# ArbPwrBoost_P7.net
KiCad netlist of a schematic drawn in Altium Designer
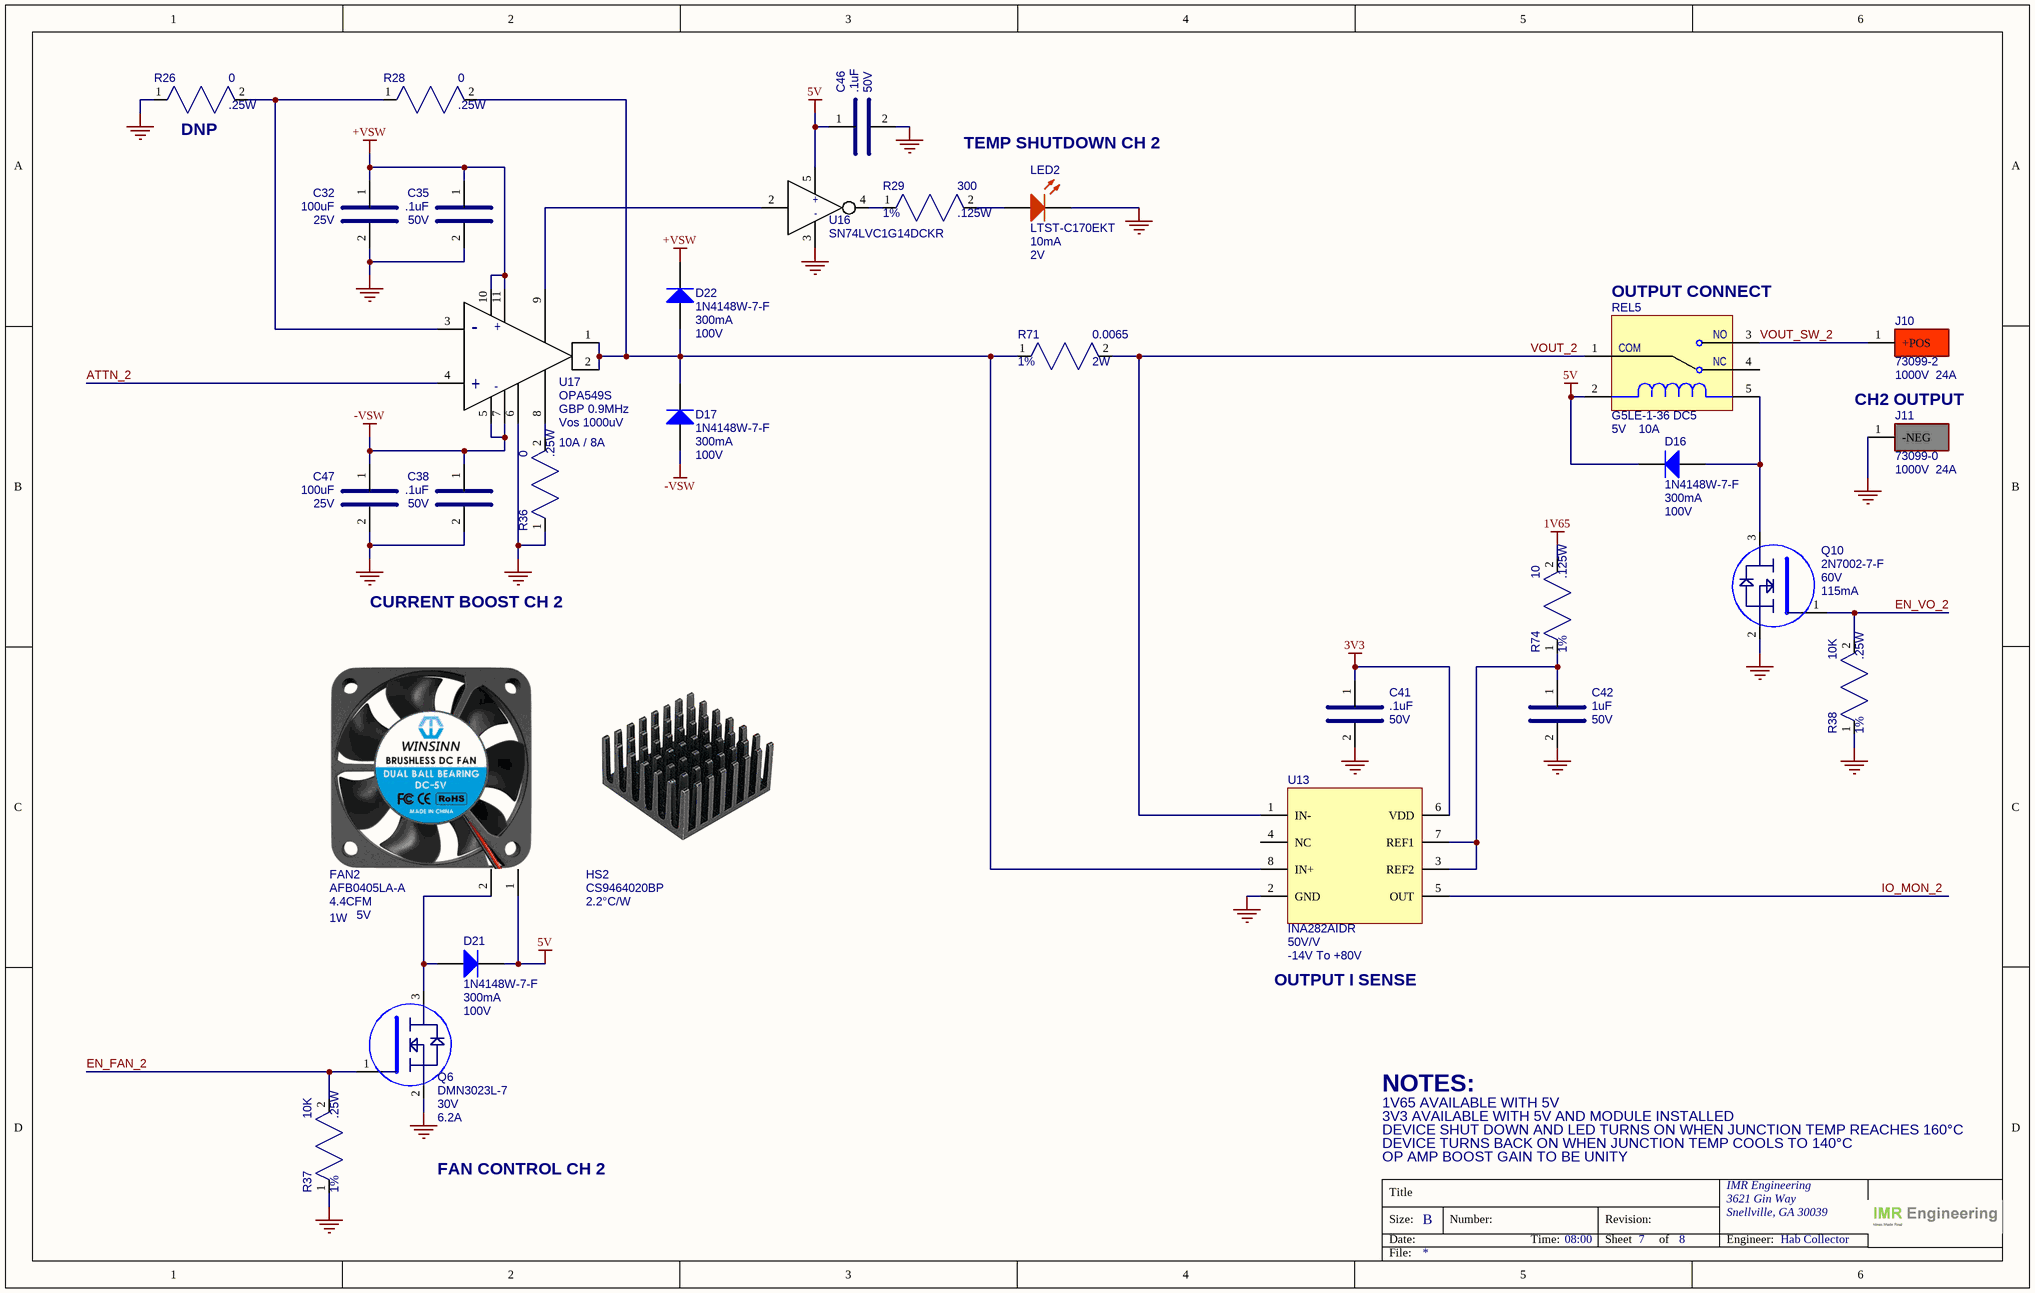
[diagram p0: ArbPwrBoost_P7.SchDoc]

(export (version "E")
  (design (tool "Eeschema 10.0.6"))
  (components
    (comp (ref "C32")
      (value "100uF")
      (footprint "CAPC6153X670N")
      (description "CAP CER 100UF 25V X7S SMD")
      (fields
        (field (name "MFG") "Murata Electronics")
        (field (name "VOLTAGE") "25V")
        (field (name "Comment") "KCM55WC71E107MH13L")
      )
      (libsource (lib "IMR_LIB_SCH_R2") (part "CAP_SMD_100UF_25V_SMD"))
    )
    (comp (ref "C35")
      (value ".1uF")
      (footprint "CAP_0805")
      (description "CAP CER 0.1UF 50V X7R 0805")
      (fields
        (field (name "MFG") "KYOCERA AVX")
        (field (name "VOLTAGE") "50V")
        (field (name "Comment") "KGM21NR71H104KT")
      )
      (libsource (lib "IMR_LIB_SCH_R2") (part "CAP_SMD_0.1UF_50V_0805"))
    )
    (comp (ref "C38")
      (value ".1uF")
      (footprint "CAP_0805")
      (description "CAP CER 0.1UF 50V X7R 0805")
      (fields
        (field (name "MFG") "KYOCERA AVX")
        (field (name "VOLTAGE") "50V")
        (field (name "Comment") "KGM21NR71H104KT")
      )
      (libsource (lib "IMR_LIB_SCH_R2") (part "CAP_SMD_0.1UF_50V_0805"))
    )
    (comp (ref "C41")
      (value ".1uF")
      (footprint "CAP_0805")
      (description "CAP CER 0.1UF 50V X7R 0805")
      (fields
        (field (name "MFG") "KYOCERA AVX")
        (field (name "VOLTAGE") "50V")
        (field (name "Comment") "KGM21NR71H104KT")
      )
      (libsource (lib "IMR_LIB_SCH_R2") (part "CAP_SMD_0.1UF_50V_0805"))
    )
    (comp (ref "C42")
      (value "1uF")
      (footprint "CAP_0805")
      (description "CAP CER 1UF 50V X7R 0805")
      (fields
        (field (name "MFG") "KYOCERA AVX")
        (field (name "VOLTAGE") "50V")
        (field (name "Comment") "08055C105K4T2A")
      )
      (libsource (lib "IMR_LIB_SCH_R2") (part "CAP_SMD_1UF_50V_0805"))
    )
    (comp (ref "C46")
      (value ".1uF")
      (footprint "CAP_0805")
      (description "CAP CER 0.1UF 50V X7R 0805")
      (fields
        (field (name "MFG") "KYOCERA AVX")
        (field (name "VOLTAGE") "50V")
        (field (name "Comment") "KGM21NR71H104KT")
      )
      (libsource (lib "IMR_LIB_SCH_R2") (part "CAP_SMD_0.1UF_50V_0805"))
    )
    (comp (ref "C47")
      (value "100uF")
      (footprint "CAPC6153X670N")
      (description "CAP CER 100UF 25V X7S SMD")
      (fields
        (field (name "MFG") "Murata Electronics")
        (field (name "VOLTAGE") "25V")
        (field (name "Comment") "KCM55WC71E107MH13L")
      )
      (libsource (lib "IMR_LIB_SCH_R2") (part "CAP_SMD_100UF_25V_SMD"))
    )
    (comp (ref "D16")
      (value "100V")
      (footprint "SOD123")
      (description "RELAY REED SPDT 250MA 5V")
      (fields
        (field (name "MFG") "Diodes Inc")
        (field (name "MFG_PN") "1N4148W-7-F")
        (field (name "CURRENT") "300mA")
        (field (name "Comment") "1N4148W-7-F")
      )
      (libsource (lib "IMR_LIB_SCH_R2") (part "DIODE_1N4148W-7-F"))
    )
    (comp (ref "D17")
      (value "100V")
      (footprint "SOD123")
      (description "RELAY REED SPDT 250MA 5V")
      (fields
        (field (name "MFG") "Diodes Inc")
        (field (name "MFG_PN") "1N4148W-7-F")
        (field (name "CURRENT") "300mA")
        (field (name "Comment") "1N4148W-7-F")
      )
      (libsource (lib "IMR_LIB_SCH_R2") (part "DIODE_1N4148W-7-F"))
    )
    (comp (ref "D21")
      (value "100V")
      (footprint "SOD123")
      (description "RELAY REED SPDT 250MA 5V")
      (fields
        (field (name "MFG") "Diodes Inc")
        (field (name "MFG_PN") "1N4148W-7-F")
        (field (name "CURRENT") "300mA")
        (field (name "Comment") "1N4148W-7-F")
      )
      (libsource (lib "IMR_LIB_SCH_R2") (part "DIODE_1N4148W-7-F"))
    )
    (comp (ref "D22")
      (value "100V")
      (footprint "SOD123")
      (description "RELAY REED SPDT 250MA 5V")
      (fields
        (field (name "MFG") "Diodes Inc")
        (field (name "MFG_PN") "1N4148W-7-F")
        (field (name "CURRENT") "300mA")
        (field (name "Comment") "1N4148W-7-F")
      )
      (libsource (lib "IMR_LIB_SCH_R2") (part "DIODE_1N4148W-7-F"))
    )
    (comp (ref "FAN2")
      (value "AFB0405LA-A")
      (footprint "FAN_AFB0405LA-A")
      (description "FAN AXIAL 40X10MM BALL 5VDC WIRE")
      (fields
        (field (name "MFG") "Delta Electronicis")
        (field (name "MFG_PN") "AFB0405LA-A")
        (field (name "AIR FLOW") "4.4CFM")
        (field (name "VOLTAGE") "5V")
        (field (name "POWER") "1W")
      )
      (libsource (lib "IMR_LIB_SCH_R2") (part "FAN_AFB0405LA-A"))
    )
    (comp (ref "HS2")
      (value "CS9464020BP")
      (footprint "HEATSINK_CS9464020BP")
      (description "Heat Sink Aluminum Top Mount")
      (fields
        (field (name "MFG") "Cooling Source")
        (field (name "MFG_PN") "CS9464020BP")
        (field (name "THERMAL RESISTANCE") "2.2°C/W")
      )
      (libsource (lib "IMR_LIB_SCH_R2") (part "HEATSINK_CS9464020BP"))
    )
    (comp (ref "J10")
      (value "1000V")
      (footprint "Pomona_73099-2")
      (description "CONN 4mm Banana Socket Right Angle PCB RED")
      (fields
        (field (name "MFG") "Pomona")
        (field (name "MFG_PN") "73099-2")
        (field (name "CURRENT") "24A")
        (field (name "Comment") "73099-2")
      )
      (libsource (lib "IMR_LIB_SCH_R2") (part "CONN_PANOMA_73099-2"))
    )
    (comp (ref "J11")
      (value "1000V")
      (footprint "Pomona_73099-0")
      (description "CONN 4mm Banana Socket Right Angle PCB BLK")
      (fields
        (field (name "MFG") "Pomona")
        (field (name "MFG_PN") "73099-0")
        (field (name "CURRENT") "24A")
        (field (name "Comment") "73099-0")
      )
      (libsource (lib "IMR_LIB_SCH_R2") (part "CONN_PANOMA_73099-0"))
    )
    (comp (ref "LED2")
      (value "2V")
      (footprint "LED_0805")
      (description "LED RED CLEAR SMD")
      (fields
        (field (name "MFG") "Diodes Inc")
        (field (name "MFG_PN") "LTST-C170EKT")
        (field (name "CURRENT") "10mA")
        (field (name "Comment") "LTST-C170EKT")
      )
      (libsource (lib "IMR_LIB_SCH_R2") (part "LED_RED_LTST-C170EKT"))
    )
    (comp (ref "Q6")
      (value "30V")
      (footprint "SOT-23")
      (description "MOSFET N-CH 30V 6.2A SOT23-3")
      (fields
        (field (name "MFG") "Diodes Inc")
        (field (name "MFG_PN") "DMN3023L-7")
        (field (name "CURRENT") "6.2A")
        (field (name "Comment") "DMN3023L-7")
      )
      (libsource (lib "IMR_LIB_SCH_R2") (part "MOSFET_NCH_DMN3023L-7"))
    )
    (comp (ref "Q10")
      (value "60V")
      (footprint "SOT-23")
      (description "MOSFET N-CH 60V 115MA SOT23-3")
      (fields
        (field (name "MFG") "Diodes Inc")
        (field (name "MFG_PN") "2N7002-7-F")
        (field (name "CURRENT") "115mA")
        (field (name "Comment") "2N7002-7-F")
      )
      (libsource (lib "IMR_LIB_SCH_R2") (part "MOSFET_NCH_2N7002-7-F"))
    )
    (comp (ref "R26")
      (value "0")
      (footprint "RES_0805")
      (description "RES SMD 0 OHM 1% 1/8W 0805")
      (fields (field (name "MFG") "Yageo") (field (name "TOLERANCE") "1%") (field (name "POWER") ".25W"))
      (libsource (lib "IMR_LIB_SCH_R2") (part "RES_SMD_0_0805_1/8W_1%"))
    )
    (comp (ref "R28")
      (value "0")
      (footprint "RES_0805")
      (description "RES SMD 0 OHM 1% 1/8W 0805")
      (fields (field (name "MFG") "Yageo") (field (name "TOLERANCE") "1%") (field (name "POWER") ".25W"))
      (libsource (lib "IMR_LIB_SCH_R2") (part "RES_SMD_0_0805_1/8W_1%"))
    )
    (comp (ref "R29")
      (value "300")
      (footprint "RES_0805")
      (description "RES SMD 300 OHM 1% 1/8W 0805")
      (fields
        (field (name "MFG") "Yageo")
        (field (name "POWER") ".125W")
        (field (name "TOLERANCE") "1%")
        (field (name "Comment") "RC0805FR-07300RL")
      )
      (libsource (lib "IMR_LIB_SCH_R2") (part "RES_SMD_300_0805_1/8W_1%"))
    )
    (comp (ref "R36")
      (value "0")
      (footprint "RES_0805")
      (description "RES SMD 0 OHM 1% 1/8W 0805")
      (fields (field (name "MFG") "Yageo") (field (name "TOLERANCE") "1%") (field (name "POWER") ".25W"))
      (libsource (lib "IMR_LIB_SCH_R2") (part "RES_SMD_0_0805_1/8W_1%"))
    )
    (comp (ref "R37")
      (value "10K")
      (footprint "RES_0805")
      (description "RES SMD 10K OHM 1% 1/4W 0805")
      (fields
        (field (name "MFG") "Yageo")
        (field (name "POWER") ".25W")
        (field (name "TOLERANCE") "1%")
        (field (name "Comment") "RC0805FR-7W10KL")
      )
      (libsource (lib "IMR_LIB_SCH_R2") (part "RES_SMD_10K_0805_1/4W_1%"))
    )
    (comp (ref "R38")
      (value "10K")
      (footprint "RES_0805")
      (description "RES SMD 10K OHM 1% 1/4W 0805")
      (fields
        (field (name "MFG") "Yageo")
        (field (name "POWER") ".25W")
        (field (name "TOLERANCE") "1%")
        (field (name "Comment") "RC0805FR-7W10KL")
      )
      (libsource (lib "IMR_LIB_SCH_R2") (part "RES_SMD_10K_0805_1/4W_1%"))
    )
    (comp (ref "R71")
      (value "0.0065")
      (footprint "RES_2512")
      (description "RES SMD 0.0065 OHM 1% 2W 2512")
      (fields
        (field (name "MFG") "Vishay Dale")
        (field (name "TOLERANCE") "1%")
        (field (name "POWER") "2W")
        (field (name "Comment") "WSL25126L500FEA18")
      )
      (libsource (lib "IMR_LIB_SCH_R2") (part "RES_SMD_0.0065_2512_2W_1%"))
    )
    (comp (ref "R74")
      (value "10")
      (footprint "RES_0805")
      (description "RES SMD 10 OHM 1% 1/8W 0805")
      (fields
        (field (name "MFG") "Yageo")
        (field (name "POWER") ".125W")
        (field (name "TOLERANCE") "1%")
        (field (name "Comment") "RC0805FR-1310RL")
      )
      (libsource (lib "IMR_LIB_SCH_R2") (part "RES_SMD_10_0805_1/8W_1%"))
    )
    (comp (ref "REL5")
      (value "5V")
      (footprint "G5LE")
      (description "RELAY GEN PURPOSE SPDT 10A 5V")
      (fields
        (field (name "MFG") "Omron")
        (field (name "MFG_PN") "G5LE-1-36 DC5")
        (field (name "CURRENT") "10A")
        (field (name "Comment") "G5LE-1-36 DC5")
      )
      (libsource (lib "IMR_LIB_SCH_R2") (part "RELAY_G5LE-1-36 DC5"))
    )
    (comp (ref "U13")
      (value "50V/V")
      (footprint "SOIC-8_54")
      (description "IC CURRENT SENSE 0.4% 50V/V SOIC-8")
      (fields
        (field (name "MFG") "Texas Instruments")
        (field (name "COMMON MODE") "-14V To +80V")
        (field (name "MFG_PN") "INA282AIDR")
        (field (name "Comment") "INA282AIDR")
      )
      (libsource (lib "IMR_LIB_SCH_R2") (part "IC_INA282AIDR"))
    )
    (comp (ref "U16")
      (value "SN74LVC1G14DCKR")
      (footprint "SOT-353")
      (description "IC INVERT SCHMITT 1CH 1IN SC70-5")
      (fields (field (name "MFG") "Texas Instruments") (field (name "MFG_PN") "SN74LVC1G14DCKR"))
      (libsource (lib "IMR_LIB_SCH_R2") (part "IC_SN74LVC1G14DCKR"))
    )
    (comp (ref "U17")
      (value "GBP 0.9MHz")
      (footprint "POWER_PACKAGE_11")
      (description "IC OPAMP POWER 1 CIRC 11PWRPACK")
      (fields
        (field (name "MFG") "Texas Instruments")
        (field (name "MFG_PN") "OPA549S")
        (field (name "VOS") "Vos 1000uV")
        (field (name "PEAK / CONTINEOUS CURRENT") "10A / 8A")
        (field (name "Comment") "OPA549S")
      )
      (libsource (lib "IMR_LIB_SCH_R2") (part "OPAMP_OPA549S"))
    )
  )
  (nets
    (net (code "1") (name "+VSW") (class "Default")
      (node (ref "C32") (pin "1") (pinfunction "1_1") (pintype "passive"))
      (node (ref "C35") (pin "1") (pinfunction "1_1") (pintype "passive"))
      (node (ref "D22") (pin "2") (pinfunction "K_2") (pintype "passive"))
      (node (ref "U17") (pin "10") (pintype "passive"))
      (node (ref "U17") (pin "11") (pintype "passive"))
    )
    (net (code "2") (name "-VSW") (class "Default")
      (node (ref "C38") (pin "1") (pinfunction "1_1") (pintype "passive"))
      (node (ref "C47") (pin "1") (pinfunction "1_1") (pintype "passive"))
      (node (ref "D17") (pin "1") (pinfunction "A_1") (pintype "passive"))
      (node (ref "U17") (pin "5") (pintype "passive"))
      (node (ref "U17") (pin "7") (pintype "passive"))
    )
    (net (code "3") (name "/ATTN_2") (class "Default")
      (node (ref "U17") (pin "4") (pinfunction "+_4") (pintype "passive"))
    )
    (net (code "4") (name "/EN_FAN_2") (class "Default")
      (node (ref "Q6") (pin "1") (pinfunction "B_1") (pintype "passive"))
      (node (ref "R37") (pin "2") (pinfunction "2_2") (pintype "passive"))
    )
    (net (code "5") (name "/EN_VO_2") (class "Default")
      (node (ref "Q10") (pin "1") (pinfunction "B_1") (pintype "passive"))
      (node (ref "R38") (pin "2") (pinfunction "2_2") (pintype "passive"))
    )
    (net (code "6") (name "/IO_MON_2") (class "Default")
      (node (ref "U13") (pin "5") (pinfunction "OUT_5") (pintype "passive"))
    )
    (net (code "7") (name "/VOUT_2") (class "Default")
      (node (ref "R71") (pin "2") (pinfunction "2_2") (pintype "passive"))
      (node (ref "REL5") (pin "1") (pinfunction "COM_1") (pintype "passive"))
      (node (ref "U13") (pin "1") (pinfunction "IN-_1") (pintype "passive"))
    )
    (net (code "8") (name "/VOUT_SW_2") (class "Default")
      (node (ref "J10") (pin "1") (pinfunction "+POS_1") (pintype "passive"))
      (node (ref "REL5") (pin "3") (pinfunction "NO_3") (pintype "passive"))
    )
    (net (code "9") (name "1V65") (class "Default")
      (node (ref "R74") (pin "2") (pinfunction "2_2") (pintype "passive"))
    )
    (net (code "10") (name "3V3") (class "Default")
      (node (ref "C41") (pin "1") (pinfunction "1_1") (pintype "passive"))
      (node (ref "U13") (pin "6") (pinfunction "VDD_6") (pintype "passive"))
    )
    (net (code "11") (name "5V") (class "Default")
      (node (ref "C46") (pin "1") (pinfunction "1_1") (pintype "passive"))
      (node (ref "D16") (pin "2") (pinfunction "K_2") (pintype "passive"))
      (node (ref "D21") (pin "2") (pinfunction "K_2") (pintype "passive"))
      (node (ref "FAN2") (pin "1") (pinfunction "1_1") (pintype "passive"))
      (node (ref "REL5") (pin "2") (pintype "passive"))
      (node (ref "U16") (pin "5") (pintype "passive"))
    )
    (net (code "12") (name "GND") (class "Default")
      (node (ref "C32") (pin "2") (pinfunction "2_2") (pintype "passive"))
      (node (ref "C35") (pin "2") (pinfunction "2_2") (pintype "passive"))
      (node (ref "C38") (pin "2") (pinfunction "2_2") (pintype "passive"))
      (node (ref "C41") (pin "2") (pinfunction "2_2") (pintype "passive"))
      (node (ref "C42") (pin "2") (pinfunction "2_2") (pintype "passive"))
      (node (ref "C46") (pin "2") (pinfunction "2_2") (pintype "passive"))
      (node (ref "C47") (pin "2") (pinfunction "2_2") (pintype "passive"))
      (node (ref "J11") (pin "1") (pinfunction "-NEG_1") (pintype "passive"))
      (node (ref "LED2") (pin "K") (pinfunction "K_K") (pintype "passive"))
      (node (ref "Q10") (pin "2") (pinfunction "E_2") (pintype "passive"))
      (node (ref "Q6") (pin "2") (pinfunction "E_2") (pintype "passive"))
      (node (ref "R26") (pin "1") (pinfunction "1_1") (pintype "passive"))
      (node (ref "R36") (pin "1") (pinfunction "1_1") (pintype "passive"))
      (node (ref "R37") (pin "1") (pinfunction "1_1") (pintype "passive"))
      (node (ref "R38") (pin "1") (pinfunction "1_1") (pintype "passive"))
      (node (ref "U13") (pin "2") (pinfunction "GND_2") (pintype "passive"))
      (node (ref "U16") (pin "3") (pintype "passive"))
      (node (ref "U17") (pin "6") (pintype "passive"))
    )
    (net (code "13") (name "Net-(D16-A)") (class "Default")
      (node (ref "D16") (pin "1") (pinfunction "A_1") (pintype "passive"))
      (node (ref "Q10") (pin "3") (pinfunction "C_3") (pintype "passive"))
      (node (ref "REL5") (pin "5") (pintype "passive"))
    )
    (net (code "14") (name "Net-(D17-K)") (class "Default")
      (node (ref "D17") (pin "2") (pinfunction "K_2") (pintype "passive"))
      (node (ref "D22") (pin "1") (pinfunction "A_1") (pintype "passive"))
      (node (ref "R28") (pin "2") (pinfunction "2_2") (pintype "passive"))
      (node (ref "R71") (pin "1") (pinfunction "1_1") (pintype "passive"))
      (node (ref "U13") (pin "8") (pinfunction "IN+_8") (pintype "passive"))
      (node (ref "U17") (pin "1") (pintype "passive"))
      (node (ref "U17") (pin "2") (pintype "passive"))
    )
    (net (code "15") (name "Net-(D21-A)") (class "Default")
      (node (ref "D21") (pin "1") (pinfunction "A_1") (pintype "passive"))
      (node (ref "FAN2") (pin "2") (pinfunction "2_2") (pintype "passive"))
      (node (ref "Q6") (pin "3") (pinfunction "C_3") (pintype "passive"))
    )
    (net (code "16") (name "Net-(LED2-PadA)") (class "Default")
      (node (ref "LED2") (pin "A") (pinfunction "A_A") (pintype "passive"))
      (node (ref "R29") (pin "2") (pinfunction "2_2") (pintype "passive"))
    )
    (net (code "17") (name "Net-(R36-Pad2)") (class "Default")
      (node (ref "R36") (pin "2") (pinfunction "2_2") (pintype "passive"))
      (node (ref "U17") (pin "8") (pintype "passive"))
    )
    (net (code "18") (name "Net-(U13-REF1)") (class "Default")
      (node (ref "C42") (pin "1") (pinfunction "1_1") (pintype "passive"))
      (node (ref "R74") (pin "1") (pinfunction "1_1") (pintype "passive"))
      (node (ref "U13") (pin "3") (pinfunction "REF2_3") (pintype "passive"))
      (node (ref "U13") (pin "7") (pinfunction "REF1_7") (pintype "passive"))
    )
    (net (code "19") (name "Net-(U16-A)") (class "Default")
      (node (ref "U16") (pin "2") (pinfunction "A_2") (pintype "passive"))
      (node (ref "U17") (pin "9") (pintype "passive"))
    )
    (net (code "20") (name "Net-(U16-Y)") (class "Default")
      (node (ref "R29") (pin "1") (pinfunction "1_1") (pintype "passive"))
      (node (ref "U16") (pin "4") (pinfunction "Y_4") (pintype "passive"))
    )
    (net (code "21") (name "Net-(U17--)") (class "Default")
      (node (ref "R26") (pin "2") (pinfunction "2_2") (pintype "passive"))
      (node (ref "R28") (pin "1") (pinfunction "1_1") (pintype "passive"))
      (node (ref "U17") (pin "3") (pinfunction "-_3") (pintype "passive"))
    )
    (net (code "22") (name "unconnected-(REL5-NC-Pad4)") (class "Default")
      (node (ref "REL5") (pin "4") (pinfunction "NC_4") (pintype "passive"))
    )
    (net (code "23") (name "unconnected-(U13-NC-Pad4)") (class "Default")
      (node (ref "U13") (pin "4") (pinfunction "NC_4") (pintype "passive"))
    )
  )
)
